# laminator.net
KiCad netlist of a schematic drawn in EAGLE
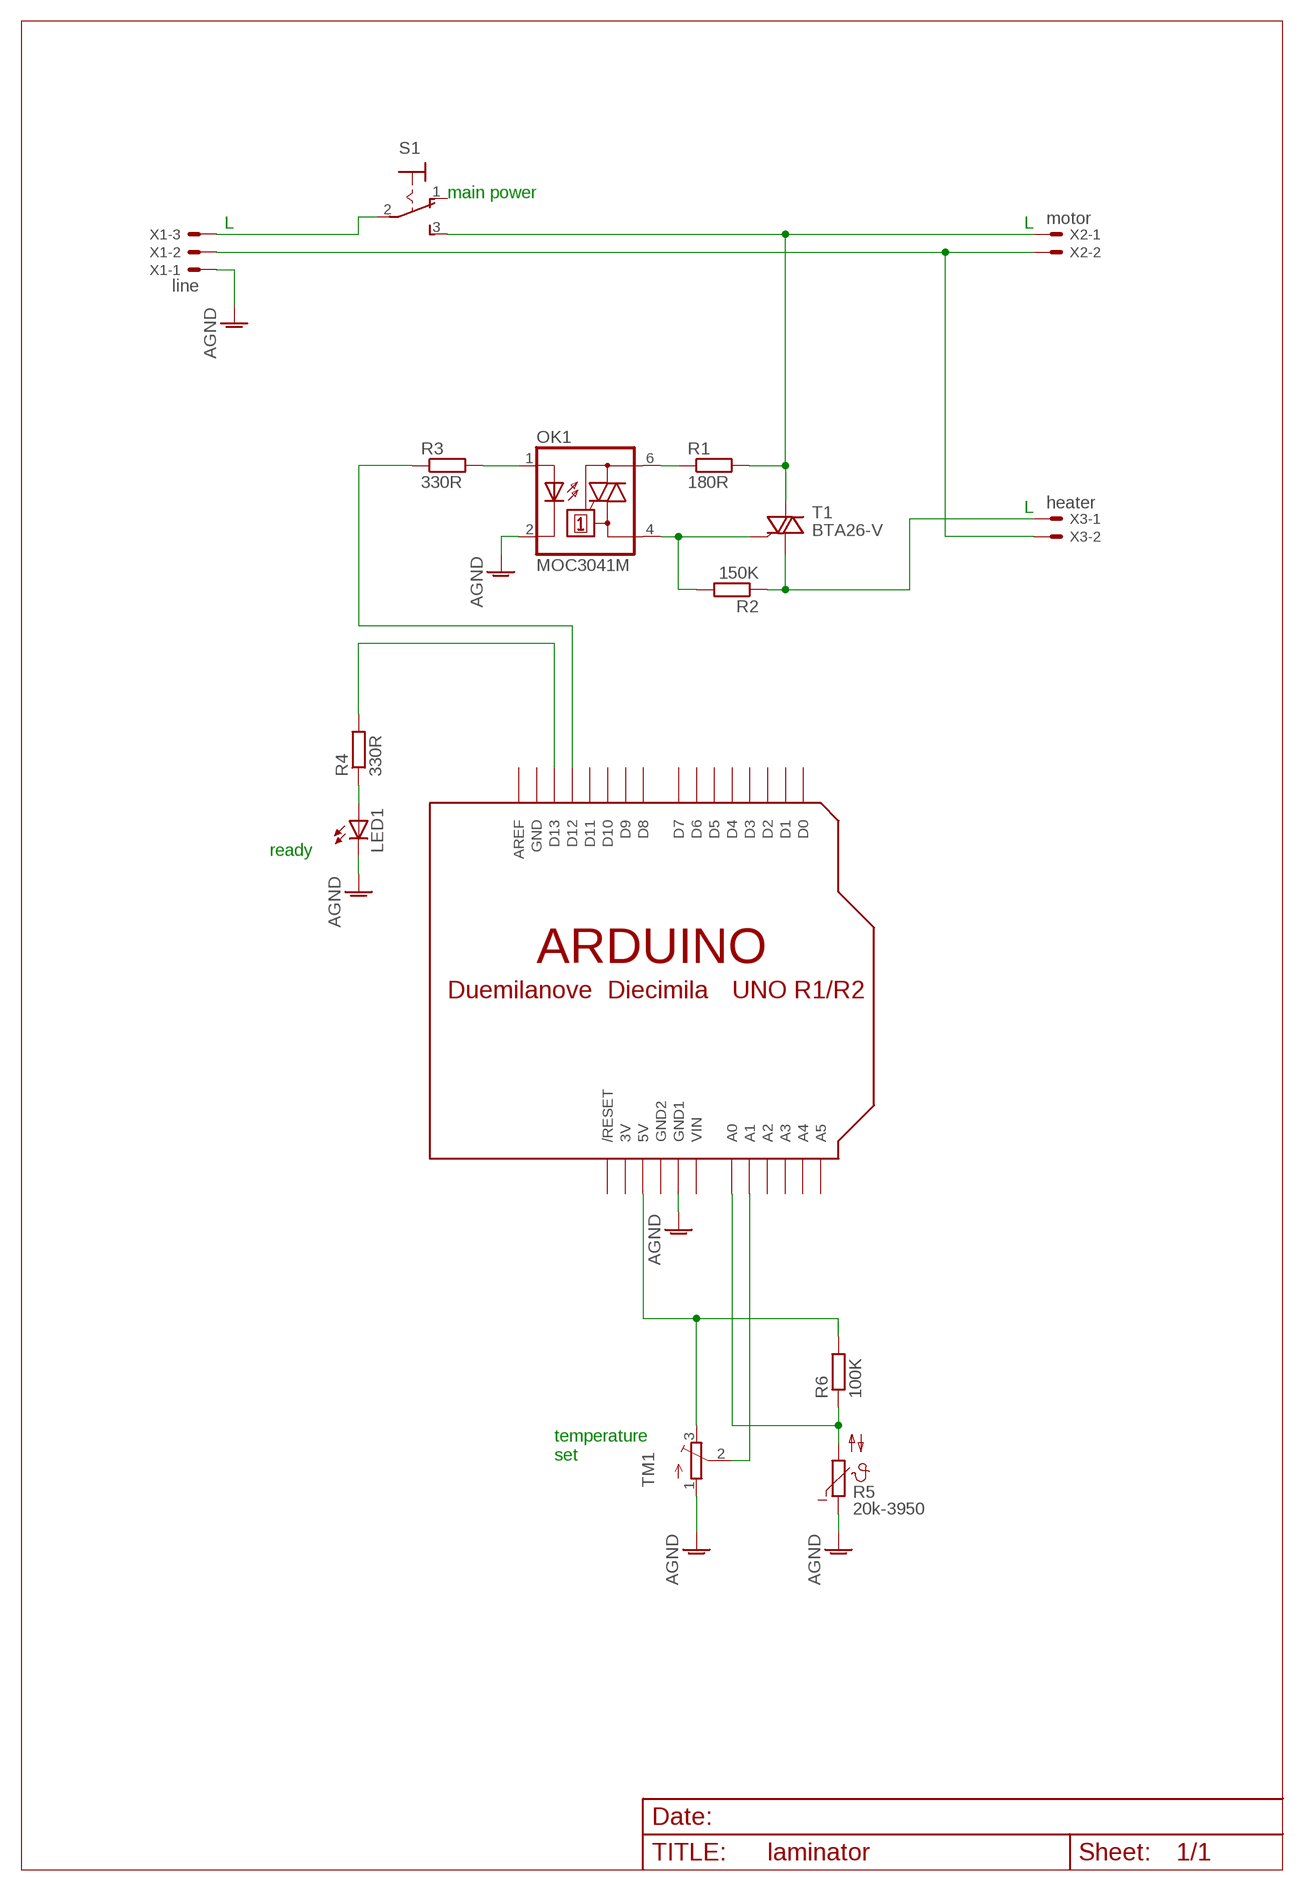
[diagram p0: schematic, sheet 1]

(export (version "E")
  (design (tool "Eeschema 10.0.6"))
  (components
    (comp (ref "LED1")
      (value "LED5MM")
      (footprint "eagle-import:LED5MM")
      (libsource (lib "eagle-import") (part "LED5MM"))
    )
    (comp (ref "OK1")
      (value "MOC3041M")
      (footprint "eagle-import:DIL06")
      (fields (field (name "MF") "FAIRCHILD SEMICONDUCTOR"))
      (libsource (lib "eagle-import") (part "MOC3041M"))
    )
    (comp (ref "R1")
      (value "180R")
      (footprint "eagle-import:0207_7")
      (libsource (lib "eagle-import") (part "R-EU_0207/7"))
    )
    (comp (ref "R2")
      (value "150K")
      (footprint "eagle-import:0207_7")
      (libsource (lib "eagle-import") (part "R-EU_0207/7"))
    )
    (comp (ref "R3")
      (value "330R")
      (footprint "eagle-import:0207_7")
      (libsource (lib "eagle-import") (part "R-EU_0207/7"))
    )
    (comp (ref "R4")
      (value "330R")
      (footprint "eagle-import:0207_7")
      (libsource (lib "eagle-import") (part "R-EU_0207/7"))
    )
    (comp (ref "R5")
      (value "20k-3950")
      (footprint "eagle-import:P640")
      (libsource (lib "eagle-import") (part "NTC640"))
    )
    (comp (ref "R6")
      (value "100K")
      (footprint "eagle-import:0207_7")
      (libsource (lib "eagle-import") (part "R-EU_0207/7"))
    )
    (comp (ref "S1")
      (value "M9040P")
      (footprint "eagle-import:M9040P")
      (libsource (lib "eagle-import") (part "M9040P"))
    )
    (comp (ref "T1")
      (value "BTA26-V")
      (footprint "eagle-import:TOP3S-1")
      (libsource (lib "eagle-import") (part "BTA26-V"))
    )
    (comp (ref "TM1")
      (value "TRIMPOT3386")
      (footprint "eagle-import:TRIM-3386")
      (libsource (lib "eagle-import") (part "TRIMPOT3386"))
    )
    (comp (ref "U$1")
      (value "ARDUINO-BPLACE")
      (footprint "eagle-import:ARDUINO-BPLACE")
      (libsource (lib "eagle-import") (part "ARDUINO-BPLACE"))
    )
    (comp (ref "X1")
      (value "line")
      (footprint "eagle-import:22-23-2031")
      (fields (field (name "MF") "MOLEX") (field (name "MPN") "22-23-2031"))
      (libsource (lib "eagle-import") (part "22-23-2031"))
    )
    (comp (ref "X2")
      (value "motor")
      (footprint "eagle-import:22-23-2021")
      (fields (field (name "MF") "MOLEX") (field (name "MPN") "22-23-2021"))
      (libsource (lib "eagle-import") (part "22-23-2021"))
    )
    (comp (ref "X3")
      (value "heater")
      (footprint "eagle-import:22-23-2021")
      (fields (field (name "MF") "MOLEX") (field (name "MPN") "22-23-2021"))
      (libsource (lib "eagle-import") (part "22-23-2021"))
    )
  )
  (nets
    (net (code "1") (name "/3V") (class "Default")
      (node (ref "U$1") (pin "3V") (pinfunction "3V_3V") (pintype "power_in"))
    )
    (net (code "2") (name "/GND") (class "Default")
      (node (ref "U$1") (pin "GND") (pinfunction "GND_GND") (pintype "power_in"))
    )
    (net (code "3") (name "/GND2") (class "Default")
      (node (ref "U$1") (pin "GND2") (pinfunction "GND2_GND2") (pintype "power_in"))
    )
    (net (code "4") (name "/VIN") (class "Default")
      (node (ref "U$1") (pin "VIN") (pinfunction "VIN_VIN") (pintype "power_in"))
    )
    (net (code "5") (name "AGND") (class "Default")
      (node (ref "LED1") (pin "K") (pinfunction "C_K") (pintype "passive"))
      (node (ref "OK1") (pin "2") (pinfunction "C_2") (pintype "passive"))
      (node (ref "R5") (pin "1") (pinfunction "1_1") (pintype "passive"))
      (node (ref "TM1") (pin "1") (pinfunction "A_1") (pintype "passive"))
      (node (ref "U$1") (pin "GND1") (pinfunction "GND1_GND1") (pintype "power_in"))
      (node (ref "X1") (pin "1") (pinfunction "S_1") (pintype "passive"))
    )
    (net (code "6") (name "Net-(LED1-PadA)") (class "Default")
      (node (ref "LED1") (pin "A") (pinfunction "A_A") (pintype "passive"))
      (node (ref "R4") (pin "1") (pinfunction "1_1") (pintype "passive"))
    )
    (net (code "7") (name "Net-(OK1-A)") (class "Default")
      (node (ref "OK1") (pin "1") (pinfunction "A_1") (pintype "passive"))
      (node (ref "R3") (pin "2") (pinfunction "2_2") (pintype "passive"))
    )
    (net (code "8") (name "Net-(OK1-A1)") (class "Default")
      (node (ref "OK1") (pin "4") (pinfunction "A1_4") (pintype "passive"))
      (node (ref "R2") (pin "2") (pinfunction "2_2") (pintype "passive"))
      (node (ref "T1") (pin "G") (pinfunction "G_G") (pintype "passive"))
    )
    (net (code "9") (name "Net-(OK1-A2)") (class "Default")
      (node (ref "OK1") (pin "6") (pinfunction "A2_6") (pintype "passive"))
      (node (ref "R1") (pin "1") (pinfunction "1_1") (pintype "passive"))
    )
    (net (code "10") (name "Net-(R3-Pad1)") (class "Default")
      (node (ref "R3") (pin "1") (pinfunction "1_1") (pintype "passive"))
      (node (ref "U$1") (pin "D12") (pinfunction "D12_D12") (pintype "bidirectional"))
    )
    (net (code "11") (name "Net-(R4-Pad2)") (class "Default")
      (node (ref "R4") (pin "2") (pinfunction "2_2") (pintype "passive"))
      (node (ref "U$1") (pin "D13") (pinfunction "D13_D13") (pintype "bidirectional"))
    )
    (net (code "12") (name "Net-(R5-Pad2)") (class "Default")
      (node (ref "R5") (pin "2") (pinfunction "2_2") (pintype "passive"))
      (node (ref "R6") (pin "1") (pinfunction "1_1") (pintype "passive"))
      (node (ref "U$1") (pin "A0") (pinfunction "A0_A0") (pintype "bidirectional"))
    )
    (net (code "13") (name "Net-(S1-P)") (class "Default")
      (node (ref "S1") (pin "2") (pinfunction "P_2") (pintype "passive"))
      (node (ref "X1") (pin "3") (pinfunction "S_3") (pintype "passive"))
    )
    (net (code "14") (name "Net-(S1-S)") (class "Default")
      (node (ref "R1") (pin "2") (pinfunction "2_2") (pintype "passive"))
      (node (ref "S1") (pin "3") (pinfunction "S_3") (pintype "passive"))
      (node (ref "T1") (pin "A2") (pinfunction "A2_A2") (pintype "passive"))
      (node (ref "X2") (pin "1") (pinfunction "S_1") (pintype "passive"))
    )
    (net (code "15") (name "Net-(TM1-E)") (class "Default")
      (node (ref "R6") (pin "2") (pinfunction "2_2") (pintype "passive"))
      (node (ref "TM1") (pin "3") (pinfunction "E_3") (pintype "passive"))
      (node (ref "U$1") (pin "5V") (pinfunction "5V_5V") (pintype "power_in"))
    )
    (net (code "16") (name "Net-(TM1-S)") (class "Default")
      (node (ref "TM1") (pin "2") (pinfunction "S_2") (pintype "passive"))
      (node (ref "U$1") (pin "A1") (pinfunction "A1_A1") (pintype "bidirectional"))
    )
    (net (code "17") (name "Net-(X1B-S)") (class "Default")
      (node (ref "X1") (pin "2") (pinfunction "S_2") (pintype "passive"))
      (node (ref "X2") (pin "2") (pinfunction "S_2") (pintype "passive"))
      (node (ref "X3") (pin "2") (pinfunction "S_2") (pintype "passive"))
    )
    (net (code "18") (name "Net-(X3A-S)") (class "Default")
      (node (ref "R2") (pin "1") (pinfunction "1_1") (pintype "passive"))
      (node (ref "T1") (pin "A1") (pinfunction "A1_A1") (pintype "passive"))
      (node (ref "X3") (pin "1") (pinfunction "S_1") (pintype "passive"))
    )
    (net (code "19") (name "unconnected-(S1-O-Pad1)") (class "Default")
      (node (ref "S1") (pin "1") (pinfunction "O_1") (pintype "passive"))
    )
    (net (code "20") (name "unconnected-(U$1-PadA2)") (class "Default")
      (node (ref "U$1") (pin "A2") (pinfunction "A2_A2") (pintype "bidirectional"))
    )
    (net (code "21") (name "unconnected-(U$1-PadA3)") (class "Default")
      (node (ref "U$1") (pin "A3") (pinfunction "A3_A3") (pintype "bidirectional"))
    )
    (net (code "22") (name "unconnected-(U$1-PadA4)") (class "Default")
      (node (ref "U$1") (pin "A4") (pinfunction "A4_A4") (pintype "bidirectional"))
    )
    (net (code "23") (name "unconnected-(U$1-PadA5)") (class "Default")
      (node (ref "U$1") (pin "A5") (pinfunction "A5_A5") (pintype "bidirectional"))
    )
    (net (code "24") (name "unconnected-(U$1-PadAREF)") (class "Default")
      (node (ref "U$1") (pin "AREF") (pinfunction "AREF_AREF") (pintype "bidirectional"))
    )
    (net (code "25") (name "unconnected-(U$1-PadD0)") (class "Default")
      (node (ref "U$1") (pin "D0") (pinfunction "D0_D0") (pintype "bidirectional"))
    )
    (net (code "26") (name "unconnected-(U$1-PadD1)") (class "Default")
      (node (ref "U$1") (pin "D1") (pinfunction "D1_D1") (pintype "bidirectional"))
    )
    (net (code "27") (name "unconnected-(U$1-PadD2)") (class "Default")
      (node (ref "U$1") (pin "D2") (pinfunction "D2_D2") (pintype "bidirectional"))
    )
    (net (code "28") (name "unconnected-(U$1-PadD3)") (class "Default")
      (node (ref "U$1") (pin "D3") (pinfunction "D3_D3") (pintype "bidirectional"))
    )
    (net (code "29") (name "unconnected-(U$1-PadD4)") (class "Default")
      (node (ref "U$1") (pin "D4") (pinfunction "D4_D4") (pintype "bidirectional"))
    )
    (net (code "30") (name "unconnected-(U$1-PadD5)") (class "Default")
      (node (ref "U$1") (pin "D5") (pinfunction "D5_D5") (pintype "bidirectional"))
    )
    (net (code "31") (name "unconnected-(U$1-PadD6)") (class "Default")
      (node (ref "U$1") (pin "D6") (pinfunction "D6_D6") (pintype "bidirectional"))
    )
    (net (code "32") (name "unconnected-(U$1-PadD7)") (class "Default")
      (node (ref "U$1") (pin "D7") (pinfunction "D7_D7") (pintype "bidirectional"))
    )
    (net (code "33") (name "unconnected-(U$1-PadD8)") (class "Default")
      (node (ref "U$1") (pin "D8") (pinfunction "D8_D8") (pintype "bidirectional"))
    )
    (net (code "34") (name "unconnected-(U$1-PadD9)") (class "Default")
      (node (ref "U$1") (pin "D9") (pinfunction "D9_D9") (pintype "bidirectional"))
    )
    (net (code "35") (name "unconnected-(U$1-PadD10)") (class "Default")
      (node (ref "U$1") (pin "D10") (pinfunction "D10_D10") (pintype "bidirectional"))
    )
    (net (code "36") (name "unconnected-(U$1-PadD11)") (class "Default")
      (node (ref "U$1") (pin "D11") (pinfunction "D11_D11") (pintype "bidirectional"))
    )
    (net (code "37") (name "unconnected-(U$1-{slash}RESET-PadRESET)") (class "Default")
      (node (ref "U$1") (pin "RESET") (pinfunction "/RESET_RESET") (pintype "bidirectional"))
    )
  )
)
